# Mosfets.net
KiCad netlist of a schematic drawn in Altium Designer
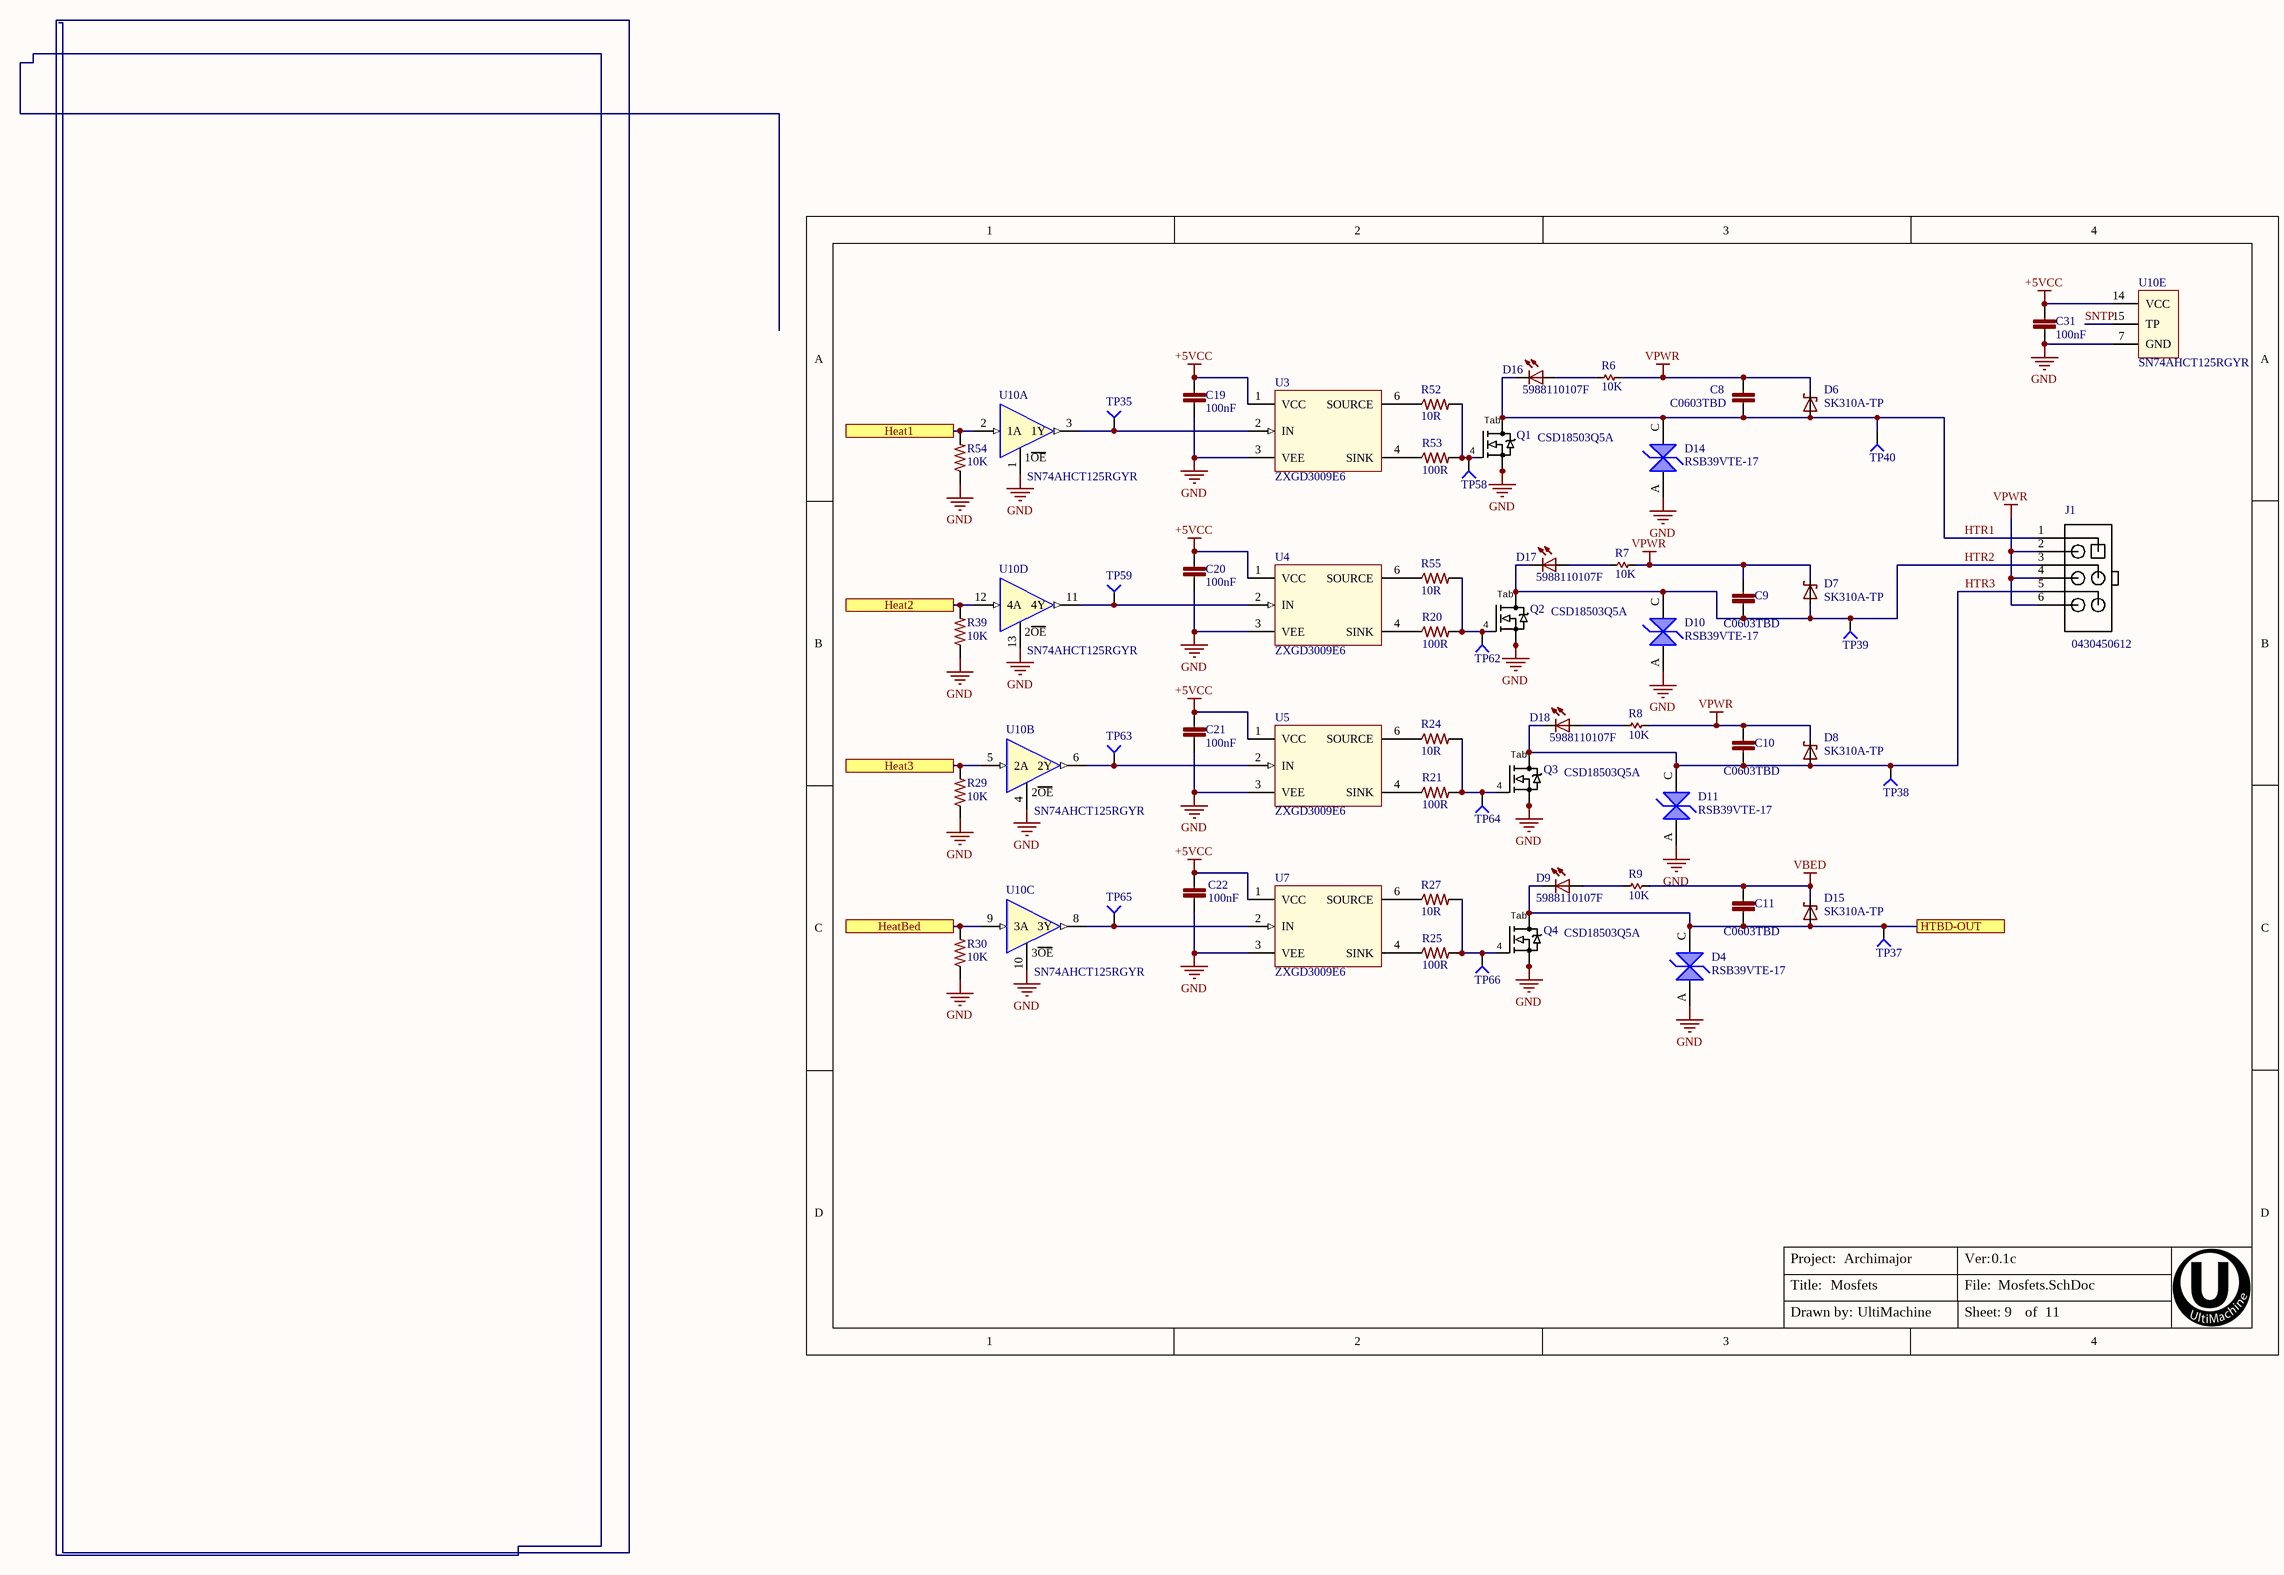
[diagram p0: Mosfets.SchDoc]

(export (version "E")
  (design (tool "Eeschema 10.0.6"))
  (components
    (comp (ref "C8")
      (value "C0603TBD")
      (footprint "C0603")
      (description "Capacitor Non Polarized")
      (fields (field (name "PART") "DNI-C0603TBD"))
      (libsource (lib "3Delight") (part "C0603TBD"))
    )
    (comp (ref "C9")
      (value "C0603TBD")
      (footprint "C0603")
      (description "Capacitor Non Polarized")
      (fields (field (name "PART") "DNI-C0603TBD"))
      (libsource (lib "3Delight") (part "C0603TBD"))
    )
    (comp (ref "C10")
      (value "C0603TBD")
      (footprint "C0603")
      (description "Capacitor Non Polarized")
      (fields (field (name "PART") "DNI-C0603TBD"))
      (libsource (lib "3Delight") (part "C0603TBD"))
    )
    (comp (ref "C11")
      (value "C0603TBD")
      (footprint "C0603")
      (description "Capacitor Non Polarized")
      (fields (field (name "PART") "DNI-C0603TBD"))
      (libsource (lib "3Delight") (part "C0603TBD"))
    )
    (comp (ref "C19")
      (value "100nF")
      (footprint "C0402")
      (description "CAP CER 0402 100nF 16V 10% X7R")
      (fields (field (name "MANUFACTURER") "Murata") (field (name "PART") "GRM155R71C104KA88D"))
      (libsource (lib "3Delight") (part "GRM155R71C104KA88D"))
    )
    (comp (ref "C20")
      (value "100nF")
      (footprint "C0402")
      (description "CAP CER 0402 100nF 16V 10% X7R")
      (fields (field (name "MANUFACTURER") "Murata") (field (name "PART") "GRM155R71C104KA88D"))
      (libsource (lib "3Delight") (part "GRM155R71C104KA88D"))
    )
    (comp (ref "C21")
      (value "100nF")
      (footprint "C0402")
      (description "CAP CER 0402 100nF 16V 10% X7R")
      (fields (field (name "MANUFACTURER") "Murata") (field (name "PART") "GRM155R71C104KA88D"))
      (libsource (lib "3Delight") (part "GRM155R71C104KA88D"))
    )
    (comp (ref "C22")
      (value "100nF")
      (footprint "C0402")
      (description "CAP CER 0402 100nF 16V 10% X7R")
      (fields (field (name "MANUFACTURER") "Murata") (field (name "PART") "GRM155R71C104KA88D"))
      (libsource (lib "") (part "GRM155R71C104KA88D_1"))
    )
    (comp (ref "C31")
      (value "100nF")
      (footprint "C0402")
      (description "CAP CER 0402 100nF 16V 10% X7R")
      (fields (field (name "MANUFACTURER") "Murata") (field (name "PART") "GRM155R71C104KA88D"))
      (libsource (lib "3Delight") (part "GRM155R71C104KA88D"))
    )
    (comp (ref "D4")
      (value "RSB39VTE-17")
      (footprint "SOD323-R")
      (description "DIODE TVS")
      (fields (field (name "MANUFACTURER") "Rohm") (field (name "TOLERANCE") "-NA-"))
      (libsource (lib "3Delight") (part "RSB39VTE-17"))
    )
    (comp (ref "D6")
      (value "SK310A-TP")
      (footprint "SMA-SM")
      (description "DIODE Schottky 3A SMA")
      (fields (field (name "MANUFACTURER") "MCC") (field (name "PART") "SK310A"))
      (libsource (lib "Archim_0.4") (part "SK310A"))
    )
    (comp (ref "D7")
      (value "SK310A-TP")
      (footprint "SMA-SM")
      (description "DIODE Schottky 3A SMA")
      (fields (field (name "MANUFACTURER") "MCC") (field (name "PART") "SK310A"))
      (libsource (lib "Archim_0.4") (part "SK310A"))
    )
    (comp (ref "D8")
      (value "SK310A-TP")
      (footprint "SMA-SM")
      (description "DIODE Schottky 3A SMA")
      (fields (field (name "MANUFACTURER") "MCC") (field (name "PART") "SK310A"))
      (libsource (lib "Archim_0.4") (part "SK310A"))
    )
    (comp (ref "D9")
      (value "Red")
      (footprint "LED2012120")
      (description "LED 0805 Red")
      (fields
        (field (name "MANUFACTURER") "Dialight")
        (field (name "PART") "5988110107F")
        (field (name "TOLERANCE") "-NA-")
      )
      (libsource (lib "3Delight") (part "5988110107F"))
    )
    (comp (ref "D10")
      (value "RSB39VTE-17")
      (footprint "SOD323-R")
      (description "DIODE TVS")
      (fields (field (name "MANUFACTURER") "Rohm") (field (name "TOLERANCE") "-NA-"))
      (libsource (lib "3Delight") (part "RSB39VTE-17"))
    )
    (comp (ref "D11")
      (value "RSB39VTE-17")
      (footprint "SOD323-R")
      (description "DIODE TVS")
      (fields (field (name "MANUFACTURER") "Rohm") (field (name "TOLERANCE") "-NA-"))
      (libsource (lib "3Delight") (part "RSB39VTE-17"))
    )
    (comp (ref "D14")
      (value "RSB39VTE-17")
      (footprint "SOD323-R")
      (description "DIODE TVS")
      (fields (field (name "MANUFACTURER") "Rohm") (field (name "TOLERANCE") "-NA-"))
      (libsource (lib "3Delight") (part "RSB39VTE-17"))
    )
    (comp (ref "D15")
      (value "SK310A-TP")
      (footprint "SMA-SM")
      (description "DIODE Schottky 3A SMA")
      (fields (field (name "MANUFACTURER") "MCC") (field (name "PART") "SK310A"))
      (libsource (lib "Archim_0.4") (part "SK310A"))
    )
    (comp (ref "D16")
      (value "Red")
      (footprint "LED2012120")
      (description "LED 0805 Red")
      (fields
        (field (name "MANUFACTURER") "Dialight")
        (field (name "PART") "5988110107F")
        (field (name "TOLERANCE") "-NA-")
      )
      (libsource (lib "3Delight") (part "5988110107F"))
    )
    (comp (ref "D17")
      (value "Red")
      (footprint "LED2012120")
      (description "LED 0805 Red")
      (fields
        (field (name "MANUFACTURER") "Dialight")
        (field (name "PART") "5988110107F")
        (field (name "TOLERANCE") "-NA-")
      )
      (libsource (lib "3Delight") (part "5988110107F"))
    )
    (comp (ref "D18")
      (value "Red")
      (footprint "LED2012120")
      (description "LED 0805 Red")
      (fields
        (field (name "MANUFACTURER") "Dialight")
        (field (name "PART") "5988110107F")
        (field (name "TOLERANCE") "-NA-")
      )
      (libsource (lib "3Delight") (part "5988110107F"))
    )
    (comp (ref "J1")
      (value "0430450612")
      (footprint "43045-0612")
      (description "Conn - 3mm Pitch Fixed")
      (fields (field (name "MANUFACTURER") "Molex"))
      (libsource (lib "Connectors") (part "Micro-Fit THT 6pos 3mm"))
    )
    (comp (ref "Q1")
      (value "CSD18503Q5A")
      (footprint "SOT669_Universal")
      (description "MOSFET N-CH 40V 100A 8VSON")
      (fields (field (name "MANUFACTURER") "TI"))
      (libsource (lib "Transistors") (part "CSD18503Q5A"))
    )
    (comp (ref "Q2")
      (value "CSD18503Q5A")
      (footprint "SOT669_Universal")
      (description "MOSFET N-CH 40V 100A 8VSON")
      (fields (field (name "MANUFACTURER") "TI"))
      (libsource (lib "Transistors") (part "CSD18503Q5A"))
    )
    (comp (ref "Q3")
      (value "CSD18503Q5A")
      (footprint "SOT669_Universal")
      (description "MOSFET N-CH 40V 100A 8VSON")
      (fields (field (name "MANUFACTURER") "TI"))
      (libsource (lib "Transistors") (part "CSD18503Q5A"))
    )
    (comp (ref "Q4")
      (value "CSD18503Q5A")
      (footprint "SOT669_Universal")
      (description "MOSFET N-CH 40V 100A 8VSON")
      (fields (field (name "MANUFACTURER") "TI"))
      (libsource (lib "Transistors") (part "CSD18503Q5A"))
    )
    (comp (ref "R6")
      (value "10K")
      (footprint "R0402")
      (description "RES SMD 10K OHM 1% 1/16W 0402")
      (fields (field (name "MANUFACTURER") "Yageo") (field (name "PART") "RC0402FR-0710KP"))
      (libsource (lib "Resistors") (part "10k 1% 0402"))
    )
    (comp (ref "R7")
      (value "10K")
      (footprint "R0402")
      (description "RES SMD 10K OHM 1% 1/16W 0402")
      (fields (field (name "MANUFACTURER") "Yageo") (field (name "PART") "RC0402FR-0710KP"))
      (libsource (lib "Resistors") (part "10k 1% 0402"))
    )
    (comp (ref "R8")
      (value "10K")
      (footprint "R0402")
      (description "RES SMD 10K OHM 1% 1/16W 0402")
      (fields (field (name "MANUFACTURER") "Yageo") (field (name "PART") "RC0402FR-0710KP"))
      (libsource (lib "Resistors") (part "10k 1% 0402"))
    )
    (comp (ref "R9")
      (value "10K")
      (footprint "R0402")
      (description "RES SMD 10K OHM 1% 1/16W 0402")
      (fields (field (name "MANUFACTURER") "Yageo") (field (name "PART") "RC0402FR-0710KP"))
      (libsource (lib "Resistors") (part "10k 1% 0402"))
    )
    (comp (ref "R20")
      (value "100R")
      (footprint "R0402")
      (description "RES SMD 100 OHM 1% 1/16W 0402")
      (fields (field (name "MANUFACTURER") "Yageo") (field (name "PART") "RC0402FR-07100RL"))
      (libsource (lib "Archim") (part "RES 100R 0402 1%"))
    )
    (comp (ref "R21")
      (value "100R")
      (footprint "R0402")
      (description "RES SMD 100 OHM 1% 1/16W 0402")
      (fields (field (name "MANUFACTURER") "Yageo") (field (name "PART") "RC0402FR-07100RL"))
      (libsource (lib "Archim") (part "RES 100R 0402 1%"))
    )
    (comp (ref "R24")
      (value "10R")
      (footprint "R0402")
      (description "RES SMD 10 OHM 1% 1/16W 0402")
      (fields (field (name "MANUFACTURER") "Yageo") (field (name "PART") "RC0402FR-0710RL"))
      (libsource (lib "3Delight") (part "RC0402FR-0710RL"))
    )
    (comp (ref "R25")
      (value "100R")
      (footprint "R0402")
      (description "RES SMD 100 OHM 1% 1/16W 0402")
      (fields (field (name "MANUFACTURER") "Yageo") (field (name "PART") "RC0402FR-07100RL"))
      (libsource (lib "Archim") (part "RES 100R 0402 1%"))
    )
    (comp (ref "R27")
      (value "10R")
      (footprint "R0402")
      (description "RES SMD 10 OHM 1% 1/16W 0402")
      (fields (field (name "MANUFACTURER") "Yageo") (field (name "PART") "RC0402FR-0710RL"))
      (libsource (lib "3Delight") (part "RC0402FR-0710RL"))
    )
    (comp (ref "R29")
      (value "10K")
      (footprint "R0402")
      (description "RES SMD 10K OHM 1% 1/16W 0402")
      (fields (field (name "MANUFACTURER") "Yageo") (field (name "PART") "RC0402FR-0710KP"))
      (libsource (lib "3Delight") (part "RC0402FR-0710KP"))
    )
    (comp (ref "R30")
      (value "10K")
      (footprint "R0402")
      (description "RES SMD 10K OHM 1% 1/16W 0402")
      (fields (field (name "MANUFACTURER") "Yageo") (field (name "PART") "RC0402FR-0710KP"))
      (libsource (lib "3Delight") (part "RC0402FR-0710KP"))
    )
    (comp (ref "R39")
      (value "10K")
      (footprint "R0402")
      (description "RES SMD 10K OHM 1% 1/16W 0402")
      (fields (field (name "MANUFACTURER") "Yageo") (field (name "PART") "RC0402FR-0710KP"))
      (libsource (lib "3Delight") (part "RC0402FR-0710KP"))
    )
    (comp (ref "R52")
      (value "10R")
      (footprint "R0402")
      (description "RES SMD 10 OHM 1% 1/16W 0402")
      (fields (field (name "MANUFACTURER") "Yageo") (field (name "PART") "RC0402FR-0710RL"))
      (libsource (lib "3Delight") (part "RC0402FR-0710RL"))
    )
    (comp (ref "R53")
      (value "100R")
      (footprint "R0402")
      (description "RES SMD 100 OHM 1% 1/16W 0402")
      (fields (field (name "MANUFACTURER") "Yageo") (field (name "PART") "RC0402FR-07100RL"))
      (libsource (lib "Archim") (part "RES 100R 0402 1%"))
    )
    (comp (ref "R54")
      (value "10K")
      (footprint "R0402")
      (description "RES SMD 10K OHM 1% 1/16W 0402")
      (fields (field (name "MANUFACTURER") "Yageo") (field (name "PART") "RC0402FR-0710KP"))
      (libsource (lib "3Delight") (part "RC0402FR-0710KP"))
    )
    (comp (ref "R55")
      (value "10R")
      (footprint "R0402")
      (description "RES SMD 10 OHM 1% 1/16W 0402")
      (fields (field (name "MANUFACTURER") "Yageo") (field (name "PART") "RC0402FR-0710RL"))
      (libsource (lib "3Delight") (part "RC0402FR-0710RL"))
    )
    (comp (ref "TP35")
      (value "TP4")
      (footprint "TP-2")
      (description "Socket")
      (fields (field (name "PART") "NOTAPART-Testpoint"))
      (libsource (lib "Archim") (part "Socket"))
    )
    (comp (ref "TP37")
      (value "TP4")
      (footprint "TP-2")
      (description "Socket")
      (fields (field (name "PART") "NOTAPART-Testpoint"))
      (libsource (lib "Archim") (part "Socket"))
    )
    (comp (ref "TP38")
      (value "TP4")
      (footprint "TP-2")
      (description "Socket")
      (fields (field (name "PART") "NOTAPART-Testpoint"))
      (libsource (lib "Archim") (part "Socket"))
    )
    (comp (ref "TP39")
      (value "TP4")
      (footprint "TP-2")
      (description "Socket")
      (fields (field (name "PART") "NOTAPART-Testpoint"))
      (libsource (lib "Archim") (part "Socket"))
    )
    (comp (ref "TP40")
      (value "TP4")
      (footprint "TP-2")
      (description "Socket")
      (fields (field (name "PART") "NOTAPART-Testpoint"))
      (libsource (lib "Archim") (part "Socket"))
    )
    (comp (ref "TP58")
      (value "TP4")
      (footprint "TP-2")
      (description "Socket")
      (fields (field (name "PART") "NOTAPART-Testpoint"))
      (libsource (lib "Archim") (part "Socket"))
    )
    (comp (ref "TP59")
      (value "TP4")
      (footprint "TP-2")
      (description "Socket")
      (fields (field (name "PART") "NOTAPART-Testpoint"))
      (libsource (lib "Archim") (part "Socket"))
    )
    (comp (ref "TP62")
      (value "TP4")
      (footprint "TP-2")
      (description "Socket")
      (fields (field (name "PART") "NOTAPART-Testpoint"))
      (libsource (lib "Archim") (part "Socket"))
    )
    (comp (ref "TP63")
      (value "TP4")
      (footprint "TP-2")
      (description "Socket")
      (fields (field (name "PART") "NOTAPART-Testpoint"))
      (libsource (lib "Archim") (part "Socket"))
    )
    (comp (ref "TP64")
      (value "TP4")
      (footprint "TP-2")
      (description "Socket")
      (fields (field (name "PART") "NOTAPART-Testpoint"))
      (libsource (lib "Archim") (part "Socket"))
    )
    (comp (ref "TP65")
      (value "TP4")
      (footprint "TP-2")
      (description "Socket")
      (fields (field (name "PART") "NOTAPART-Testpoint"))
      (libsource (lib "Archim") (part "Socket"))
    )
    (comp (ref "TP66")
      (value "TP4")
      (footprint "TP-2")
      (description "Socket")
      (fields (field (name "PART") "NOTAPART-Testpoint"))
      (libsource (lib "Archim") (part "Socket"))
    )
    (comp (ref "U3")
      (value "ZXGD3009E6")
      (footprint "SOT26P285X140-6L")
      (description "MOSFET DRVR 3A 1-OUT High Speed Non-Inv6-Pin SOT-26 T/R")
      (fields (field (name "MANUFACTURER") "Diodes Incorporated") (field (name "PART") "ZXGD3009E6TA"))
      (libsource (lib "3Delight") (part "ZXGD3009E6"))
    )
    (comp (ref "U4")
      (value "ZXGD3009E6")
      (footprint "SOT26P285X140-6L")
      (description "MOSFET DRVR 3A 1-OUT High Speed Non-Inv6-Pin SOT-26 T/R")
      (fields (field (name "MANUFACTURER") "Diodes Incorporated") (field (name "PART") "ZXGD3009E6TA"))
      (libsource (lib "3Delight") (part "ZXGD3009E6"))
    )
    (comp (ref "U5")
      (value "ZXGD3009E6")
      (footprint "SOT26P285X140-6L")
      (description "MOSFET DRVR 3A 1-OUT High Speed Non-Inv6-Pin SOT-26 T/R")
      (fields (field (name "MANUFACTURER") "Diodes Incorporated") (field (name "PART") "ZXGD3009E6TA"))
      (libsource (lib "3Delight") (part "ZXGD3009E6"))
    )
    (comp (ref "U7")
      (value "ZXGD3009E6")
      (footprint "SOT26P285X140-6L")
      (description "MOSFET DRVR 3A 1-OUT High Speed Non-Inv6-Pin SOT-26 T/R")
      (fields (field (name "MANUFACTURER") "Diodes Incorporated") (field (name "PART") "ZXGD3009E6TA"))
      (libsource (lib "3Delight") (part "ZXGD3009E6"))
    )
    (comp (ref "U10")
      (value "SN74AHCT125RGYR")
      (footprint "QFN50P350X350X100_RGY_S-PVQFN-N14")
      (description "Quadruple Bus Buffer Gates With 3-State Outputs 14-VQFN -40 to 125")
      (fields (field (name "MANUFACTURER") "Texas Instruments") (field (name "TOLERANCE") "-NA-"))
      (libsource (lib "3Delight") (part "SN74AHCT125"))
    )
  )
  (nets
    (net (code "1") (name "+5VCC") (class "Default")
      (node (ref "C19") (pin "2") (pinfunction "2_2") (pintype "passive"))
      (node (ref "C20") (pin "2") (pinfunction "2_2") (pintype "passive"))
      (node (ref "C21") (pin "2") (pinfunction "2_2") (pintype "passive"))
      (node (ref "C22") (pin "1") (pinfunction "1_1") (pintype "passive"))
      (node (ref "C31") (pin "2") (pinfunction "2_2") (pintype "passive"))
      (node (ref "U10") (pin "14") (pinfunction "VCC_14") (pintype "power_in"))
      (node (ref "U3") (pin "1") (pinfunction "VCC_1") (pintype "power_in"))
      (node (ref "U4") (pin "1") (pinfunction "VCC_1") (pintype "power_in"))
      (node (ref "U5") (pin "1") (pinfunction "VCC_1") (pintype "power_in"))
      (node (ref "U7") (pin "1") (pinfunction "VCC_1") (pintype "power_in"))
    )
    (net (code "2") (name "/HTBD-OUT") (class "Default")
      (node (ref "C11") (pin "2") (pinfunction "2_2") (pintype "passive"))
      (node (ref "D15") (pin "A") (pinfunction "A_A") (pintype "passive"))
      (node (ref "D4") (pin "C") (pinfunction "C_C") (pintype "power_in"))
      (node (ref "D9") (pin "C") (pinfunction "C_C") (pintype "passive"))
      (node (ref "Q4") (pin "TAB") (pinfunction "D_TAB") (pintype "passive"))
      (node (ref "TP37") (pin "1") (pinfunction "1_1") (pintype "passive"))
    )
    (net (code "3") (name "/HTR1") (class "Default")
      (node (ref "C8") (pin "2") (pinfunction "2_2") (pintype "passive"))
      (node (ref "D14") (pin "C") (pinfunction "C_C") (pintype "power_in"))
      (node (ref "D16") (pin "C") (pinfunction "C_C") (pintype "passive"))
      (node (ref "D6") (pin "A") (pinfunction "A_A") (pintype "passive"))
      (node (ref "J1") (pin "1") (pinfunction "1_1") (pintype "power_in"))
      (node (ref "Q1") (pin "TAB") (pinfunction "D_TAB") (pintype "passive"))
      (node (ref "TP40") (pin "1") (pinfunction "1_1") (pintype "passive"))
    )
    (net (code "4") (name "/HTR2") (class "Default")
      (node (ref "C9") (pin "2") (pinfunction "2_2") (pintype "passive"))
      (node (ref "D10") (pin "C") (pinfunction "C_C") (pintype "power_in"))
      (node (ref "D17") (pin "C") (pinfunction "C_C") (pintype "passive"))
      (node (ref "D7") (pin "A") (pinfunction "A_A") (pintype "passive"))
      (node (ref "J1") (pin "3") (pinfunction "3_3") (pintype "power_in"))
      (node (ref "Q2") (pin "TAB") (pinfunction "D_TAB") (pintype "passive"))
      (node (ref "TP39") (pin "1") (pinfunction "1_1") (pintype "passive"))
    )
    (net (code "5") (name "/HTR3") (class "Default")
      (node (ref "C10") (pin "2") (pinfunction "2_2") (pintype "passive"))
      (node (ref "D11") (pin "C") (pinfunction "C_C") (pintype "power_in"))
      (node (ref "D18") (pin "C") (pinfunction "C_C") (pintype "passive"))
      (node (ref "D8") (pin "A") (pinfunction "A_A") (pintype "passive"))
      (node (ref "J1") (pin "5") (pinfunction "5_5") (pintype "power_in"))
      (node (ref "Q3") (pin "TAB") (pinfunction "D_TAB") (pintype "passive"))
      (node (ref "TP38") (pin "1") (pinfunction "1_1") (pintype "passive"))
    )
    (net (code "6") (name "/Heat1") (class "Default")
      (node (ref "R54") (pin "2") (pinfunction "2_2") (pintype "passive"))
      (node (ref "U10") (pin "2") (pinfunction "1A_2") (pintype "input"))
    )
    (net (code "7") (name "/Heat2") (class "Default")
      (node (ref "R39") (pin "2") (pinfunction "2_2") (pintype "passive"))
      (node (ref "U10") (pin "12") (pinfunction "4A_12") (pintype "input"))
    )
    (net (code "8") (name "/Heat3") (class "Default")
      (node (ref "R29") (pin "2") (pinfunction "2_2") (pintype "passive"))
      (node (ref "U10") (pin "5") (pinfunction "2A_5") (pintype "input"))
    )
    (net (code "9") (name "/HeatBed") (class "Default")
      (node (ref "R30") (pin "2") (pinfunction "2_2") (pintype "passive"))
      (node (ref "U10") (pin "9") (pinfunction "3A_9") (pintype "input"))
    )
    (net (code "10") (name "/SNTP") (class "Default")
      (node (ref "U10") (pin "15") (pinfunction "TP_15") (pintype "power_in"))
    )
    (net (code "11") (name "GND") (class "Default")
      (node (ref "C19") (pin "1") (pinfunction "1_1") (pintype "passive"))
      (node (ref "C20") (pin "1") (pinfunction "1_1") (pintype "passive"))
      (node (ref "C21") (pin "1") (pinfunction "1_1") (pintype "passive"))
      (node (ref "C22") (pin "2") (pinfunction "2_2") (pintype "passive"))
      (node (ref "C31") (pin "1") (pinfunction "1_1") (pintype "passive"))
      (node (ref "D10") (pin "A") (pinfunction "A_A") (pintype "power_in"))
      (node (ref "D11") (pin "A") (pinfunction "A_A") (pintype "power_in"))
      (node (ref "D14") (pin "A") (pinfunction "A_A") (pintype "power_in"))
      (node (ref "D4") (pin "A") (pinfunction "A_A") (pintype "power_in"))
      (node (ref "Q1") (pin "1") (pinfunction "S_1") (pintype "passive"))
      (node (ref "Q1") (pin "2") (pinfunction "S_2") (pintype "passive"))
      (node (ref "Q1") (pin "3") (pinfunction "S_3") (pintype "passive"))
      (node (ref "Q2") (pin "1") (pinfunction "S_1") (pintype "passive"))
      (node (ref "Q2") (pin "2") (pinfunction "S_2") (pintype "passive"))
      (node (ref "Q2") (pin "3") (pinfunction "S_3") (pintype "passive"))
      (node (ref "Q3") (pin "1") (pinfunction "S_1") (pintype "passive"))
      (node (ref "Q3") (pin "2") (pinfunction "S_2") (pintype "passive"))
      (node (ref "Q3") (pin "3") (pinfunction "S_3") (pintype "passive"))
      (node (ref "Q4") (pin "1") (pinfunction "S_1") (pintype "passive"))
      (node (ref "Q4") (pin "2") (pinfunction "S_2") (pintype "passive"))
      (node (ref "Q4") (pin "3") (pinfunction "S_3") (pintype "passive"))
      (node (ref "R29") (pin "1") (pinfunction "1_1") (pintype "passive"))
      (node (ref "R30") (pin "1") (pinfunction "1_1") (pintype "passive"))
      (node (ref "R39") (pin "1") (pinfunction "1_1") (pintype "passive"))
      (node (ref "R54") (pin "1") (pinfunction "1_1") (pintype "passive"))
      (node (ref "U10") (pin "1") (pinfunction "1OE_1") (pintype "power_in"))
      (node (ref "U10") (pin "10") (pinfunction "3OE_10") (pintype "power_in"))
      (node (ref "U10") (pin "13") (pinfunction "4OE_13") (pintype "power_in"))
      (node (ref "U10") (pin "4") (pinfunction "2OE_4") (pintype "power_in"))
      (node (ref "U10") (pin "7") (pinfunction "GND_7") (pintype "power_in"))
      (node (ref "U3") (pin "3") (pinfunction "VEE_3") (pintype "power_in"))
      (node (ref "U4") (pin "3") (pinfunction "VEE_3") (pintype "power_in"))
      (node (ref "U5") (pin "3") (pinfunction "VEE_3") (pintype "power_in"))
      (node (ref "U7") (pin "3") (pinfunction "VEE_3") (pintype "power_in"))
    )
    (net (code "12") (name "Net-(D9-PadA)") (class "Default")
      (node (ref "D9") (pin "A") (pinfunction "A_A") (pintype "passive"))
      (node (ref "R9") (pin "1") (pinfunction "1_1") (pintype "passive"))
    )
    (net (code "13") (name "Net-(D16-PadA)") (class "Default")
      (node (ref "D16") (pin "A") (pinfunction "A_A") (pintype "passive"))
      (node (ref "R6") (pin "1") (pinfunction "1_1") (pintype "passive"))
    )
    (net (code "14") (name "Net-(D17-PadA)") (class "Default")
      (node (ref "D17") (pin "A") (pinfunction "A_A") (pintype "passive"))
      (node (ref "R7") (pin "1") (pinfunction "1_1") (pintype "passive"))
    )
    (net (code "15") (name "Net-(D18-PadA)") (class "Default")
      (node (ref "D18") (pin "A") (pinfunction "A_A") (pintype "passive"))
      (node (ref "R8") (pin "1") (pinfunction "1_1") (pintype "passive"))
    )
    (net (code "16") (name "Net-(Q1-G)") (class "Default")
      (node (ref "Q1") (pin "4") (pinfunction "G_4") (pintype "passive"))
      (node (ref "R52") (pin "2") (pinfunction "2_2") (pintype "passive"))
      (node (ref "R53") (pin "2") (pinfunction "2_2") (pintype "passive"))
      (node (ref "TP58") (pin "1") (pinfunction "1_1") (pintype "passive"))
    )
    (net (code "17") (name "Net-(Q2-G)") (class "Default")
      (node (ref "Q2") (pin "4") (pinfunction "G_4") (pintype "passive"))
      (node (ref "R20") (pin "2") (pinfunction "2_2") (pintype "passive"))
      (node (ref "R55") (pin "2") (pinfunction "2_2") (pintype "passive"))
      (node (ref "TP62") (pin "1") (pinfunction "1_1") (pintype "passive"))
    )
    (net (code "18") (name "Net-(Q3-G)") (class "Default")
      (node (ref "Q3") (pin "4") (pinfunction "G_4") (pintype "passive"))
      (node (ref "R21") (pin "2") (pinfunction "2_2") (pintype "passive"))
      (node (ref "R24") (pin "2") (pinfunction "2_2") (pintype "passive"))
      (node (ref "TP64") (pin "1") (pinfunction "1_1") (pintype "passive"))
    )
    (net (code "19") (name "Net-(Q4-G)") (class "Default")
      (node (ref "Q4") (pin "4") (pinfunction "G_4") (pintype "passive"))
      (node (ref "R25") (pin "2") (pinfunction "2_2") (pintype "passive"))
      (node (ref "R27") (pin "2") (pinfunction "2_2") (pintype "passive"))
      (node (ref "TP66") (pin "1") (pinfunction "1_1") (pintype "passive"))
    )
    (net (code "20") (name "Net-(U3-SINK)") (class "Default")
      (node (ref "R53") (pin "1") (pinfunction "1_1") (pintype "passive"))
      (node (ref "U3") (pin "4") (pinfunction "SINK_4") (pintype "power_in"))
    )
    (net (code "21") (name "Net-(U3-SOURCE)") (class "Default")
      (node (ref "R52") (pin "1") (pinfunction "1_1") (pintype "passive"))
      (node (ref "U3") (pin "6") (pinfunction "SOURCE_6") (pintype "power_in"))
    )
    (net (code "22") (name "Net-(U4-SINK)") (class "Default")
      (node (ref "R20") (pin "1") (pinfunction "1_1") (pintype "passive"))
      (node (ref "U4") (pin "4") (pinfunction "SINK_4") (pintype "power_in"))
    )
    (net (code "23") (name "Net-(U4-SOURCE)") (class "Default")
      (node (ref "R55") (pin "1") (pinfunction "1_1") (pintype "passive"))
      (node (ref "U4") (pin "6") (pinfunction "SOURCE_6") (pintype "power_in"))
    )
    (net (code "24") (name "Net-(U5-SINK)") (class "Default")
      (node (ref "R21") (pin "1") (pinfunction "1_1") (pintype "passive"))
      (node (ref "U5") (pin "4") (pinfunction "SINK_4") (pintype "power_in"))
    )
    (net (code "25") (name "Net-(U5-SOURCE)") (class "Default")
      (node (ref "R24") (pin "1") (pinfunction "1_1") (pintype "passive"))
      (node (ref "U5") (pin "6") (pinfunction "SOURCE_6") (pintype "power_in"))
    )
    (net (code "26") (name "Net-(U7-SINK)") (class "Default")
      (node (ref "R25") (pin "1") (pinfunction "1_1") (pintype "passive"))
      (node (ref "U7") (pin "4") (pinfunction "SINK_4") (pintype "power_in"))
    )
    (net (code "27") (name "Net-(U7-SOURCE)") (class "Default")
      (node (ref "R27") (pin "1") (pinfunction "1_1") (pintype "passive"))
      (node (ref "U7") (pin "6") (pinfunction "SOURCE_6") (pintype "power_in"))
    )
    (net (code "28") (name "Net-(U10A-1Y)") (class "Default")
      (node (ref "TP35") (pin "1") (pinfunction "1_1") (pintype "passive"))
      (node (ref "U10") (pin "3") (pinfunction "1Y_3") (pintype "output"))
      (node (ref "U3") (pin "2") (pinfunction "IN_2") (pintype "input"))
    )
    (net (code "29") (name "Net-(U10B-2Y)") (class "Default")
      (node (ref "TP63") (pin "1") (pinfunction "1_1") (pintype "passive"))
      (node (ref "U10") (pin "6") (pinfunction "2Y_6") (pintype "output"))
      (node (ref "U5") (pin "2") (pinfunction "IN_2") (pintype "input"))
    )
    (net (code "30") (name "Net-(U10C-3Y)") (class "Default")
      (node (ref "TP65") (pin "1") (pinfunction "1_1") (pintype "passive"))
      (node (ref "U10") (pin "8") (pinfunction "3Y_8") (pintype "output"))
      (node (ref "U7") (pin "2") (pinfunction "IN_2") (pintype "input"))
    )
    (net (code "31") (name "Net-(U10D-4Y)") (class "Default")
      (node (ref "TP59") (pin "1") (pinfunction "1_1") (pintype "passive"))
      (node (ref "U10") (pin "11") (pinfunction "4Y_11") (pintype "output"))
      (node (ref "U4") (pin "2") (pinfunction "IN_2") (pintype "input"))
    )
    (net (code "32") (name "VBED") (class "Default")
      (node (ref "C11") (pin "1") (pinfunction "1_1") (pintype "passive"))
      (node (ref "D15") (pin "C") (pinfunction "C_C") (pintype "passive"))
      (node (ref "R9") (pin "2") (pinfunction "2_2") (pintype "passive"))
    )
    (net (code "33") (name "VPWR") (class "Default")
      (node (ref "C10") (pin "1") (pinfunction "1_1") (pintype "passive"))
      (node (ref "C8") (pin "1") (pinfunction "1_1") (pintype "passive"))
      (node (ref "C9") (pin "1") (pinfunction "1_1") (pintype "passive"))
      (node (ref "D6") (pin "C") (pinfunction "C_C") (pintype "passive"))
      (node (ref "D7") (pin "C") (pinfunction "C_C") (pintype "passive"))
      (node (ref "D8") (pin "C") (pinfunction "C_C") (pintype "passive"))
      (node (ref "J1") (pin "2") (pinfunction "2_2") (pintype "power_in"))
      (node (ref "J1") (pin "4") (pinfunction "4_4") (pintype "power_in"))
      (node (ref "J1") (pin "6") (pinfunction "6_6") (pintype "power_in"))
      (node (ref "R6") (pin "2") (pinfunction "2_2") (pintype "passive"))
      (node (ref "R7") (pin "2") (pinfunction "2_2") (pintype "passive"))
      (node (ref "R8") (pin "2") (pinfunction "2_2") (pintype "passive"))
    )
  )
)
